# segundero.net
KiCad netlist of a schematic drawn in EAGLE
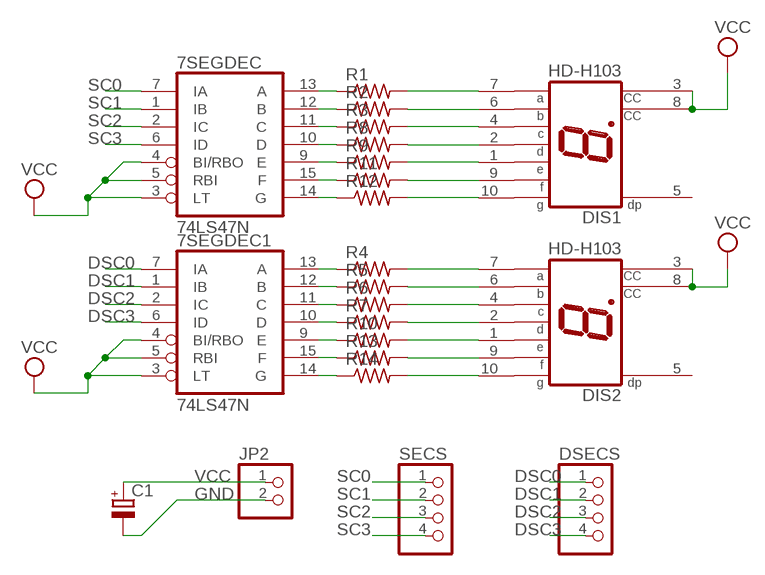
[diagram p0: schematic, sheet 1]

(export (version "E")
  (design (tool "Eeschema 10.0.6"))
  (components
    (comp (ref "7SEGDEC")
      (value "74LS47N")
      (footprint "eagle-import:DIL16")
      (libsource (lib "eagle-import") (part "7447NLS"))
    )
    (comp (ref "7SEGDEC1")
      (value "74LS47N")
      (footprint "eagle-import:DIL16")
      (libsource (lib "eagle-import") (part "7447NLS"))
    )
    (comp (ref "C1")
      (value "CPOL-EUE2-5")
      (footprint "eagle-import:E2-5")
      (libsource (lib "eagle-import") (part "CPOL-EUE2-5"))
    )
    (comp (ref "DIS1")
      (value "HD-H103")
      (footprint "eagle-import:HDSP-M")
      (libsource (lib "eagle-import") (part "HD-H103"))
    )
    (comp (ref "DIS2")
      (value "HD-H103")
      (footprint "eagle-import:HDSP-M")
      (libsource (lib "eagle-import") (part "HD-H103"))
    )
    (comp (ref "DSECS")
      (value "PINHD-1X4")
      (footprint "eagle-import:1X04")
      (libsource (lib "eagle-import") (part "PINHD-1X4"))
    )
    (comp (ref "JP2")
      (value "PINHD-1X2")
      (footprint "eagle-import:1X02")
      (libsource (lib "eagle-import") (part "PINHD-1X2"))
    )
    (comp (ref "R1")
      (value "R-US_0204/7")
      (footprint "eagle-import:0204_7")
      (libsource (lib "eagle-import") (part "R-US_0204/7"))
    )
    (comp (ref "R2")
      (value "R-US_0204/7")
      (footprint "eagle-import:0204_7")
      (libsource (lib "eagle-import") (part "R-US_0204/7"))
    )
    (comp (ref "R3")
      (value "R-US_0204/7")
      (footprint "eagle-import:0204_7")
      (libsource (lib "eagle-import") (part "R-US_0204/7"))
    )
    (comp (ref "R4")
      (value "R-US_0204/7")
      (footprint "eagle-import:0204_7")
      (libsource (lib "eagle-import") (part "R-US_0204/7"))
    )
    (comp (ref "R5")
      (value "R-US_0204/7")
      (footprint "eagle-import:0204_7")
      (libsource (lib "eagle-import") (part "R-US_0204/7"))
    )
    (comp (ref "R6")
      (value "R-US_0204/7")
      (footprint "eagle-import:0204_7")
      (libsource (lib "eagle-import") (part "R-US_0204/7"))
    )
    (comp (ref "R7")
      (value "R-US_0204/7")
      (footprint "eagle-import:0204_7")
      (libsource (lib "eagle-import") (part "R-US_0204/7"))
    )
    (comp (ref "R8")
      (value "R-US_0204/7")
      (footprint "eagle-import:0204_7")
      (libsource (lib "eagle-import") (part "R-US_0204/7"))
    )
    (comp (ref "R9")
      (value "R-US_0204/7")
      (footprint "eagle-import:0204_7")
      (libsource (lib "eagle-import") (part "R-US_0204/7"))
    )
    (comp (ref "R10")
      (value "R-US_0204/7")
      (footprint "eagle-import:0204_7")
      (libsource (lib "eagle-import") (part "R-US_0204/7"))
    )
    (comp (ref "R11")
      (value "R-US_0204/7")
      (footprint "eagle-import:0204_7")
      (libsource (lib "eagle-import") (part "R-US_0204/7"))
    )
    (comp (ref "R12")
      (value "R-US_0204/7")
      (footprint "eagle-import:0204_7")
      (libsource (lib "eagle-import") (part "R-US_0204/7"))
    )
    (comp (ref "R13")
      (value "R-US_0204/7")
      (footprint "eagle-import:0204_7")
      (libsource (lib "eagle-import") (part "R-US_0204/7"))
    )
    (comp (ref "R14")
      (value "R-US_0204/7")
      (footprint "eagle-import:0204_7")
      (libsource (lib "eagle-import") (part "R-US_0204/7"))
    )
    (comp (ref "SECS")
      (value "PINHD-1X4")
      (footprint "eagle-import:1X04")
      (libsource (lib "eagle-import") (part "PINHD-1X4"))
    )
  )
  (nets
    (net (code "1") (name "/DSC0") (class "Default")
      (node (ref "7SEGDEC1") (pin "7") (pinfunction "IA_7") (pintype "input"))
      (node (ref "DSECS") (pin "1") (pinfunction "1_1") (pintype "passive"))
    )
    (net (code "2") (name "/DSC1") (class "Default")
      (node (ref "7SEGDEC1") (pin "1") (pinfunction "IB_1") (pintype "input"))
      (node (ref "DSECS") (pin "2") (pinfunction "2_2") (pintype "passive"))
    )
    (net (code "3") (name "/DSC2") (class "Default")
      (node (ref "7SEGDEC1") (pin "2") (pinfunction "IC_2") (pintype "input"))
      (node (ref "DSECS") (pin "3") (pinfunction "3_3") (pintype "passive"))
    )
    (net (code "4") (name "/DSC3") (class "Default")
      (node (ref "7SEGDEC1") (pin "6") (pinfunction "ID_6") (pintype "input"))
      (node (ref "DSECS") (pin "4") (pinfunction "4_4") (pintype "passive"))
    )
    (net (code "5") (name "/GND") (class "Default")
      (node (ref "C1") (pin "-") (pinfunction "-_-") (pintype "passive"))
      (node (ref "JP2") (pin "2") (pinfunction "2_2") (pintype "passive"))
    )
    (net (code "6") (name "/SC0") (class "Default")
      (node (ref "7SEGDEC") (pin "7") (pinfunction "IA_7") (pintype "input"))
      (node (ref "SECS") (pin "1") (pinfunction "1_1") (pintype "passive"))
    )
    (net (code "7") (name "/SC1") (class "Default")
      (node (ref "7SEGDEC") (pin "1") (pinfunction "IB_1") (pintype "input"))
      (node (ref "SECS") (pin "2") (pinfunction "2_2") (pintype "passive"))
    )
    (net (code "8") (name "/SC2") (class "Default")
      (node (ref "7SEGDEC") (pin "2") (pinfunction "IC_2") (pintype "input"))
      (node (ref "SECS") (pin "3") (pinfunction "3_3") (pintype "passive"))
    )
    (net (code "9") (name "/SC3") (class "Default")
      (node (ref "7SEGDEC") (pin "6") (pinfunction "ID_6") (pintype "input"))
      (node (ref "SECS") (pin "4") (pinfunction "4_4") (pintype "passive"))
    )
    (net (code "10") (name "Net-(7SEGDEC1A-A)") (class "Default")
      (node (ref "7SEGDEC1") (pin "13") (pinfunction "A_13") (pintype "output"))
      (node (ref "R4") (pin "1") (pinfunction "1_1") (pintype "passive"))
    )
    (net (code "11") (name "Net-(7SEGDEC1A-B)") (class "Default")
      (node (ref "7SEGDEC1") (pin "12") (pinfunction "B_12") (pintype "output"))
      (node (ref "R5") (pin "1") (pinfunction "1_1") (pintype "passive"))
    )
    (net (code "12") (name "Net-(7SEGDEC1A-C)") (class "Default")
      (node (ref "7SEGDEC1") (pin "11") (pinfunction "C_11") (pintype "output"))
      (node (ref "R6") (pin "1") (pinfunction "1_1") (pintype "passive"))
    )
    (net (code "13") (name "Net-(7SEGDEC1A-D)") (class "Default")
      (node (ref "7SEGDEC1") (pin "10") (pinfunction "D_10") (pintype "output"))
      (node (ref "R7") (pin "1") (pinfunction "1_1") (pintype "passive"))
    )
    (net (code "14") (name "Net-(7SEGDEC1A-E)") (class "Default")
      (node (ref "7SEGDEC1") (pin "9") (pinfunction "E_9") (pintype "output"))
      (node (ref "R10") (pin "1") (pinfunction "1_1") (pintype "passive"))
    )
    (net (code "15") (name "Net-(7SEGDEC1A-F)") (class "Default")
      (node (ref "7SEGDEC1") (pin "15") (pinfunction "F_15") (pintype "output"))
      (node (ref "R13") (pin "1") (pinfunction "1_1") (pintype "passive"))
    )
    (net (code "16") (name "Net-(7SEGDEC1A-G)") (class "Default")
      (node (ref "7SEGDEC1") (pin "14") (pinfunction "G_14") (pintype "output"))
      (node (ref "R14") (pin "1") (pinfunction "1_1") (pintype "passive"))
    )
    (net (code "17") (name "Net-(7SEGDECA-A)") (class "Default")
      (node (ref "7SEGDEC") (pin "13") (pinfunction "A_13") (pintype "output"))
      (node (ref "R1") (pin "1") (pinfunction "1_1") (pintype "passive"))
    )
    (net (code "18") (name "Net-(7SEGDECA-B)") (class "Default")
      (node (ref "7SEGDEC") (pin "12") (pinfunction "B_12") (pintype "output"))
      (node (ref "R2") (pin "1") (pinfunction "1_1") (pintype "passive"))
    )
    (net (code "19") (name "Net-(7SEGDECA-C)") (class "Default")
      (node (ref "7SEGDEC") (pin "11") (pinfunction "C_11") (pintype "output"))
      (node (ref "R3") (pin "1") (pinfunction "1_1") (pintype "passive"))
    )
    (net (code "20") (name "Net-(7SEGDECA-D)") (class "Default")
      (node (ref "7SEGDEC") (pin "10") (pinfunction "D_10") (pintype "output"))
      (node (ref "R8") (pin "1") (pinfunction "1_1") (pintype "passive"))
    )
    (net (code "21") (name "Net-(7SEGDECA-E)") (class "Default")
      (node (ref "7SEGDEC") (pin "9") (pinfunction "E_9") (pintype "output"))
      (node (ref "R9") (pin "1") (pinfunction "1_1") (pintype "passive"))
    )
    (net (code "22") (name "Net-(7SEGDECA-F)") (class "Default")
      (node (ref "7SEGDEC") (pin "15") (pinfunction "F_15") (pintype "output"))
      (node (ref "R11") (pin "1") (pinfunction "1_1") (pintype "passive"))
    )
    (net (code "23") (name "Net-(7SEGDECA-G)") (class "Default")
      (node (ref "7SEGDEC") (pin "14") (pinfunction "G_14") (pintype "output"))
      (node (ref "R12") (pin "1") (pinfunction "1_1") (pintype "passive"))
    )
    (net (code "24") (name "Net-(DIS1-A)") (class "Default")
      (node (ref "DIS1") (pin "7") (pinfunction "A_7") (pintype "passive"))
      (node (ref "R1") (pin "2") (pinfunction "2_2") (pintype "passive"))
    )
    (net (code "25") (name "Net-(DIS1-B)") (class "Default")
      (node (ref "DIS1") (pin "6") (pinfunction "B_6") (pintype "passive"))
      (node (ref "R2") (pin "2") (pinfunction "2_2") (pintype "passive"))
    )
    (net (code "26") (name "Net-(DIS1-C)") (class "Default")
      (node (ref "DIS1") (pin "4") (pinfunction "C_4") (pintype "passive"))
      (node (ref "R3") (pin "2") (pinfunction "2_2") (pintype "passive"))
    )
    (net (code "27") (name "Net-(DIS1-D)") (class "Default")
      (node (ref "DIS1") (pin "2") (pinfunction "D_2") (pintype "passive"))
      (node (ref "R8") (pin "2") (pinfunction "2_2") (pintype "passive"))
    )
    (net (code "28") (name "Net-(DIS1-E)") (class "Default")
      (node (ref "DIS1") (pin "1") (pinfunction "E_1") (pintype "passive"))
      (node (ref "R9") (pin "2") (pinfunction "2_2") (pintype "passive"))
    )
    (net (code "29") (name "Net-(DIS1-F)") (class "Default")
      (node (ref "DIS1") (pin "9") (pinfunction "F_9") (pintype "passive"))
      (node (ref "R11") (pin "2") (pinfunction "2_2") (pintype "passive"))
    )
    (net (code "30") (name "Net-(DIS1-G)") (class "Default")
      (node (ref "DIS1") (pin "10") (pinfunction "G_10") (pintype "passive"))
      (node (ref "R12") (pin "2") (pinfunction "2_2") (pintype "passive"))
    )
    (net (code "31") (name "Net-(DIS2-A)") (class "Default")
      (node (ref "DIS2") (pin "7") (pinfunction "A_7") (pintype "passive"))
      (node (ref "R4") (pin "2") (pinfunction "2_2") (pintype "passive"))
    )
    (net (code "32") (name "Net-(DIS2-B)") (class "Default")
      (node (ref "DIS2") (pin "6") (pinfunction "B_6") (pintype "passive"))
      (node (ref "R5") (pin "2") (pinfunction "2_2") (pintype "passive"))
    )
    (net (code "33") (name "Net-(DIS2-C)") (class "Default")
      (node (ref "DIS2") (pin "4") (pinfunction "C_4") (pintype "passive"))
      (node (ref "R6") (pin "2") (pinfunction "2_2") (pintype "passive"))
    )
    (net (code "34") (name "Net-(DIS2-D)") (class "Default")
      (node (ref "DIS2") (pin "2") (pinfunction "D_2") (pintype "passive"))
      (node (ref "R7") (pin "2") (pinfunction "2_2") (pintype "passive"))
    )
    (net (code "35") (name "Net-(DIS2-E)") (class "Default")
      (node (ref "DIS2") (pin "1") (pinfunction "E_1") (pintype "passive"))
      (node (ref "R10") (pin "2") (pinfunction "2_2") (pintype "passive"))
    )
    (net (code "36") (name "Net-(DIS2-F)") (class "Default")
      (node (ref "DIS2") (pin "9") (pinfunction "F_9") (pintype "passive"))
      (node (ref "R13") (pin "2") (pinfunction "2_2") (pintype "passive"))
    )
    (net (code "37") (name "Net-(DIS2-G)") (class "Default")
      (node (ref "DIS2") (pin "10") (pinfunction "G_10") (pintype "passive"))
      (node (ref "R14") (pin "2") (pinfunction "2_2") (pintype "passive"))
    )
    (net (code "38") (name "VCC") (class "Default")
      (node (ref "7SEGDEC") (pin "3") (pinfunction "LT_3") (pintype "input"))
      (node (ref "7SEGDEC") (pin "4") (pinfunction "BI/RBO_4") (pintype "input"))
      (node (ref "7SEGDEC") (pin "5") (pinfunction "RBI_5") (pintype "input"))
      (node (ref "7SEGDEC1") (pin "3") (pinfunction "LT_3") (pintype "input"))
      (node (ref "7SEGDEC1") (pin "4") (pinfunction "BI/RBO_4") (pintype "input"))
      (node (ref "7SEGDEC1") (pin "5") (pinfunction "RBI_5") (pintype "input"))
      (node (ref "C1") (pin "+") (pinfunction "+_+") (pintype "passive"))
      (node (ref "DIS1") (pin "3") (pinfunction "CC_3") (pintype "passive"))
      (node (ref "DIS1") (pin "8") (pinfunction "CC_8") (pintype "passive"))
      (node (ref "DIS2") (pin "3") (pinfunction "CC_3") (pintype "passive"))
      (node (ref "DIS2") (pin "8") (pinfunction "CC_8") (pintype "passive"))
      (node (ref "JP2") (pin "1") (pinfunction "1_1") (pintype "passive"))
    )
    (net (code "39") (name "unconnected-(DIS1-DP-Pad5)") (class "Default")
      (node (ref "DIS1") (pin "5") (pinfunction "DP_5") (pintype "passive"))
    )
    (net (code "40") (name "unconnected-(DIS2-DP-Pad5)") (class "Default")
      (node (ref "DIS2") (pin "5") (pinfunction "DP_5") (pintype "passive"))
    )
  )
)
